# cubey_v2_8step.net
KiCad netlist of a schematic drawn in EAGLE
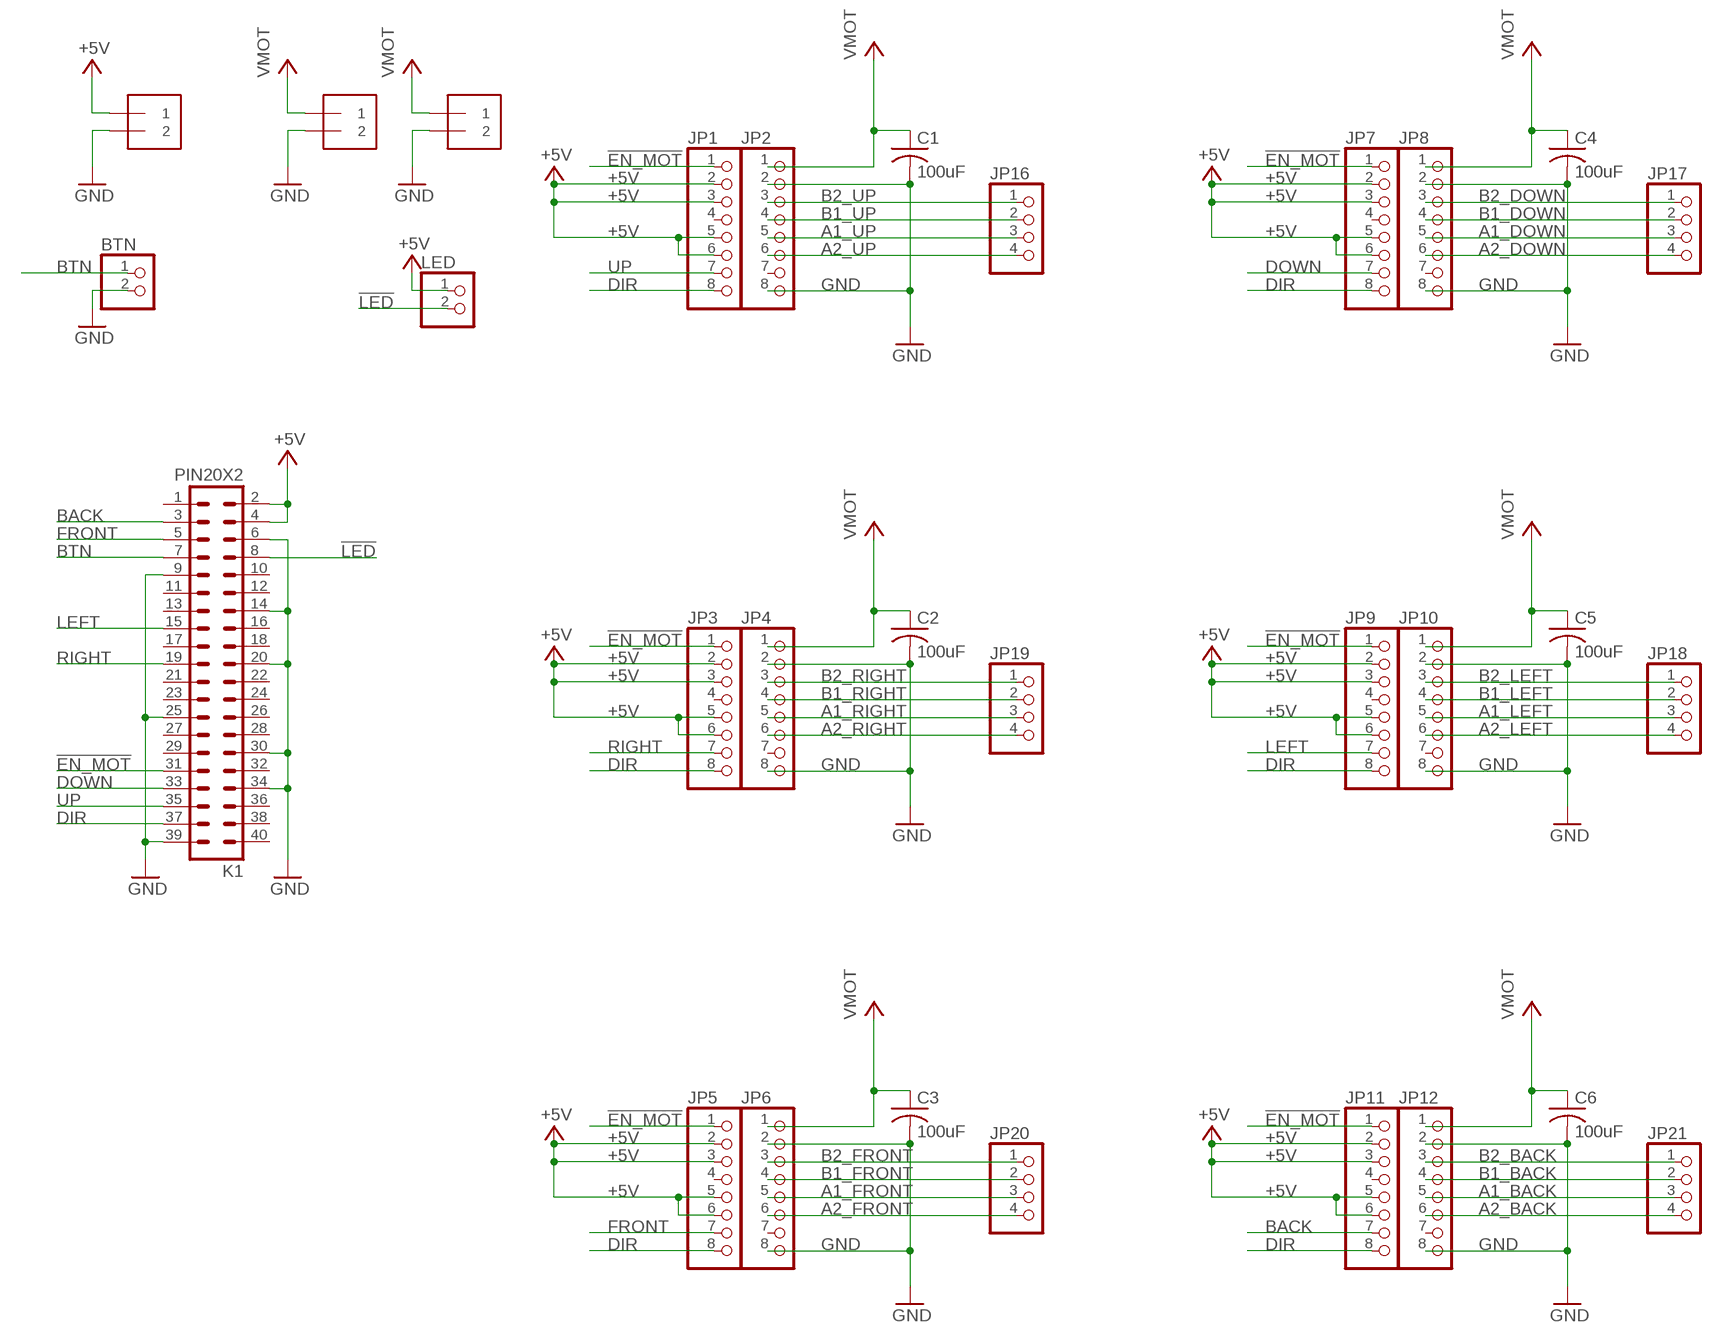
[diagram p0: schematic, sheet 1]

(export (version "E")
  (design (tool "Eeschema 10.0.6"))
  (components
    (comp (ref "5V_PWR")
      (value "1X2-3.5MM")
      (footprint "eagle-import:1X2-3.5MM")
      (libsource (lib "eagle-import") (part "1X2-3.5MM"))
    )
    (comp (ref "BTN")
      (value "PINHD-1X2")
      (footprint "eagle-import:1X02")
      (libsource (lib "eagle-import") (part "PINHD-1X2"))
    )
    (comp (ref "C1")
      (value "100uF")
      (footprint "eagle-import:C025-025X050")
      (libsource (lib "eagle-import") (part "C-US025-025X050"))
    )
    (comp (ref "C2")
      (value "100uF")
      (footprint "eagle-import:C025-025X050")
      (libsource (lib "eagle-import") (part "C-US025-025X050"))
    )
    (comp (ref "C3")
      (value "100uF")
      (footprint "eagle-import:C025-025X050")
      (libsource (lib "eagle-import") (part "C-US025-025X050"))
    )
    (comp (ref "C4")
      (value "100uF")
      (footprint "eagle-import:C025-025X050")
      (libsource (lib "eagle-import") (part "C-US025-025X050"))
    )
    (comp (ref "C5")
      (value "100uF")
      (footprint "eagle-import:C025-025X050")
      (libsource (lib "eagle-import") (part "C-US025-025X050"))
    )
    (comp (ref "C6")
      (value "100uF")
      (footprint "eagle-import:C025-025X050")
      (libsource (lib "eagle-import") (part "C-US025-025X050"))
    )
    (comp (ref "JP1")
      (value "PINHD-1X8")
      (footprint "eagle-import:1X08")
      (libsource (lib "eagle-import") (part "PINHD-1X8"))
    )
    (comp (ref "JP2")
      (value "PINHD-1X8")
      (footprint "eagle-import:1X08")
      (libsource (lib "eagle-import") (part "PINHD-1X8"))
    )
    (comp (ref "JP3")
      (value "PINHD-1X8")
      (footprint "eagle-import:1X08")
      (libsource (lib "eagle-import") (part "PINHD-1X8"))
    )
    (comp (ref "JP4")
      (value "PINHD-1X8")
      (footprint "eagle-import:1X08")
      (libsource (lib "eagle-import") (part "PINHD-1X8"))
    )
    (comp (ref "JP5")
      (value "PINHD-1X8")
      (footprint "eagle-import:1X08")
      (libsource (lib "eagle-import") (part "PINHD-1X8"))
    )
    (comp (ref "JP6")
      (value "PINHD-1X8")
      (footprint "eagle-import:1X08")
      (libsource (lib "eagle-import") (part "PINHD-1X8"))
    )
    (comp (ref "JP7")
      (value "PINHD-1X8")
      (footprint "eagle-import:1X08")
      (libsource (lib "eagle-import") (part "PINHD-1X8"))
    )
    (comp (ref "JP8")
      (value "PINHD-1X8")
      (footprint "eagle-import:1X08")
      (libsource (lib "eagle-import") (part "PINHD-1X8"))
    )
    (comp (ref "JP9")
      (value "PINHD-1X8")
      (footprint "eagle-import:1X08")
      (libsource (lib "eagle-import") (part "PINHD-1X8"))
    )
    (comp (ref "JP10")
      (value "PINHD-1X8")
      (footprint "eagle-import:1X08")
      (libsource (lib "eagle-import") (part "PINHD-1X8"))
    )
    (comp (ref "JP11")
      (value "PINHD-1X8")
      (footprint "eagle-import:1X08")
      (libsource (lib "eagle-import") (part "PINHD-1X8"))
    )
    (comp (ref "JP12")
      (value "PINHD-1X8")
      (footprint "eagle-import:1X08")
      (libsource (lib "eagle-import") (part "PINHD-1X8"))
    )
    (comp (ref "JP16")
      (value "PINHD-1X4")
      (footprint "eagle-import:1X04")
      (libsource (lib "eagle-import") (part "PINHD-1X4"))
    )
    (comp (ref "JP17")
      (value "PINHD-1X4")
      (footprint "eagle-import:1X04")
      (libsource (lib "eagle-import") (part "PINHD-1X4"))
    )
    (comp (ref "JP18")
      (value "PINHD-1X4")
      (footprint "eagle-import:1X04")
      (libsource (lib "eagle-import") (part "PINHD-1X4"))
    )
    (comp (ref "JP19")
      (value "PINHD-1X4")
      (footprint "eagle-import:1X04")
      (libsource (lib "eagle-import") (part "PINHD-1X4"))
    )
    (comp (ref "JP20")
      (value "PINHD-1X4")
      (footprint "eagle-import:1X04")
      (libsource (lib "eagle-import") (part "PINHD-1X4"))
    )
    (comp (ref "JP21")
      (value "PINHD-1X4")
      (footprint "eagle-import:1X04")
      (libsource (lib "eagle-import") (part "PINHD-1X4"))
    )
    (comp (ref "K1")
      (value "PIN20X2")
      (footprint "eagle-import:PIN_20X2")
      (libsource (lib "eagle-import") (part "PIN20X2"))
    )
    (comp (ref "LED")
      (value "PINHD-1X2")
      (footprint "eagle-import:1X02")
      (libsource (lib "eagle-import") (part "PINHD-1X2"))
    )
    (comp (ref "MOT_PWR")
      (value "1X2-3.5MM")
      (footprint "eagle-import:1X2-3.5MM")
      (libsource (lib "eagle-import") (part "1X2-3.5MM"))
    )
    (comp (ref "MOT_PWR1")
      (value "1X2-3.5MM")
      (footprint "eagle-import:1X2-3.5MM")
      (libsource (lib "eagle-import") (part "1X2-3.5MM"))
    )
  )
  (nets
    (net (code "1") (name "+5V") (class "Default")
      (node (ref "5V_PWR") (pin "1") (pinfunction "1_1") (pintype "passive"))
      (node (ref "JP1") (pin "2") (pinfunction "2_2") (pintype "passive"))
      (node (ref "JP1") (pin "3") (pinfunction "3_3") (pintype "passive"))
      (node (ref "JP1") (pin "5") (pinfunction "5_5") (pintype "passive"))
      (node (ref "JP1") (pin "6") (pinfunction "6_6") (pintype "passive"))
      (node (ref "JP11") (pin "2") (pinfunction "2_2") (pintype "passive"))
      (node (ref "JP11") (pin "3") (pinfunction "3_3") (pintype "passive"))
      (node (ref "JP11") (pin "5") (pinfunction "5_5") (pintype "passive"))
      (node (ref "JP11") (pin "6") (pinfunction "6_6") (pintype "passive"))
      (node (ref "JP3") (pin "2") (pinfunction "2_2") (pintype "passive"))
      (node (ref "JP3") (pin "3") (pinfunction "3_3") (pintype "passive"))
      (node (ref "JP3") (pin "5") (pinfunction "5_5") (pintype "passive"))
      (node (ref "JP3") (pin "6") (pinfunction "6_6") (pintype "passive"))
      (node (ref "JP5") (pin "2") (pinfunction "2_2") (pintype "passive"))
      (node (ref "JP5") (pin "3") (pinfunction "3_3") (pintype "passive"))
      (node (ref "JP5") (pin "5") (pinfunction "5_5") (pintype "passive"))
      (node (ref "JP5") (pin "6") (pinfunction "6_6") (pintype "passive"))
      (node (ref "JP7") (pin "2") (pinfunction "2_2") (pintype "passive"))
      (node (ref "JP7") (pin "3") (pinfunction "3_3") (pintype "passive"))
      (node (ref "JP7") (pin "5") (pinfunction "5_5") (pintype "passive"))
      (node (ref "JP7") (pin "6") (pinfunction "6_6") (pintype "passive"))
      (node (ref "JP9") (pin "2") (pinfunction "2_2") (pintype "passive"))
      (node (ref "JP9") (pin "3") (pinfunction "3_3") (pintype "passive"))
      (node (ref "JP9") (pin "5") (pinfunction "5_5") (pintype "passive"))
      (node (ref "JP9") (pin "6") (pinfunction "6_6") (pintype "passive"))
      (node (ref "K1") (pin "2") (pinfunction "2_2") (pintype "passive"))
      (node (ref "K1") (pin "4") (pinfunction "4_4") (pintype "passive"))
      (node (ref "LED") (pin "1") (pinfunction "1_1") (pintype "passive"))
    )
    (net (code "2") (name "/A1_BACK") (class "Default")
      (node (ref "JP12") (pin "5") (pinfunction "5_5") (pintype "passive"))
      (node (ref "JP21") (pin "3") (pinfunction "3_3") (pintype "passive"))
    )
    (net (code "3") (name "/A1_DOWN") (class "Default")
      (node (ref "JP17") (pin "3") (pinfunction "3_3") (pintype "passive"))
      (node (ref "JP8") (pin "5") (pinfunction "5_5") (pintype "passive"))
    )
    (net (code "4") (name "/A1_FRONT") (class "Default")
      (node (ref "JP20") (pin "3") (pinfunction "3_3") (pintype "passive"))
      (node (ref "JP6") (pin "5") (pinfunction "5_5") (pintype "passive"))
    )
    (net (code "5") (name "/A1_LEFT") (class "Default")
      (node (ref "JP10") (pin "5") (pinfunction "5_5") (pintype "passive"))
      (node (ref "JP18") (pin "3") (pinfunction "3_3") (pintype "passive"))
    )
    (net (code "6") (name "/A1_RIGHT") (class "Default")
      (node (ref "JP19") (pin "3") (pinfunction "3_3") (pintype "passive"))
      (node (ref "JP4") (pin "5") (pinfunction "5_5") (pintype "passive"))
    )
    (net (code "7") (name "/A1_UP") (class "Default")
      (node (ref "JP16") (pin "3") (pinfunction "3_3") (pintype "passive"))
      (node (ref "JP2") (pin "5") (pinfunction "5_5") (pintype "passive"))
    )
    (net (code "8") (name "/A2_BACK") (class "Default")
      (node (ref "JP12") (pin "6") (pinfunction "6_6") (pintype "passive"))
      (node (ref "JP21") (pin "4") (pinfunction "4_4") (pintype "passive"))
    )
    (net (code "9") (name "/A2_DOWN") (class "Default")
      (node (ref "JP17") (pin "4") (pinfunction "4_4") (pintype "passive"))
      (node (ref "JP8") (pin "6") (pinfunction "6_6") (pintype "passive"))
    )
    (net (code "10") (name "/A2_FRONT") (class "Default")
      (node (ref "JP20") (pin "4") (pinfunction "4_4") (pintype "passive"))
      (node (ref "JP6") (pin "6") (pinfunction "6_6") (pintype "passive"))
    )
    (net (code "11") (name "/A2_LEFT") (class "Default")
      (node (ref "JP10") (pin "6") (pinfunction "6_6") (pintype "passive"))
      (node (ref "JP18") (pin "4") (pinfunction "4_4") (pintype "passive"))
    )
    (net (code "12") (name "/A2_RIGHT") (class "Default")
      (node (ref "JP19") (pin "4") (pinfunction "4_4") (pintype "passive"))
      (node (ref "JP4") (pin "6") (pinfunction "6_6") (pintype "passive"))
    )
    (net (code "13") (name "/A2_UP") (class "Default")
      (node (ref "JP16") (pin "4") (pinfunction "4_4") (pintype "passive"))
      (node (ref "JP2") (pin "6") (pinfunction "6_6") (pintype "passive"))
    )
    (net (code "14") (name "/B1_BACK") (class "Default")
      (node (ref "JP12") (pin "4") (pinfunction "4_4") (pintype "passive"))
      (node (ref "JP21") (pin "2") (pinfunction "2_2") (pintype "passive"))
    )
    (net (code "15") (name "/B1_DOWN") (class "Default")
      (node (ref "JP17") (pin "2") (pinfunction "2_2") (pintype "passive"))
      (node (ref "JP8") (pin "4") (pinfunction "4_4") (pintype "passive"))
    )
    (net (code "16") (name "/B1_FRONT") (class "Default")
      (node (ref "JP20") (pin "2") (pinfunction "2_2") (pintype "passive"))
      (node (ref "JP6") (pin "4") (pinfunction "4_4") (pintype "passive"))
    )
    (net (code "17") (name "/B1_LEFT") (class "Default")
      (node (ref "JP10") (pin "4") (pinfunction "4_4") (pintype "passive"))
      (node (ref "JP18") (pin "2") (pinfunction "2_2") (pintype "passive"))
    )
    (net (code "18") (name "/B1_RIGHT") (class "Default")
      (node (ref "JP19") (pin "2") (pinfunction "2_2") (pintype "passive"))
      (node (ref "JP4") (pin "4") (pinfunction "4_4") (pintype "passive"))
    )
    (net (code "19") (name "/B1_UP") (class "Default")
      (node (ref "JP16") (pin "2") (pinfunction "2_2") (pintype "passive"))
      (node (ref "JP2") (pin "4") (pinfunction "4_4") (pintype "passive"))
    )
    (net (code "20") (name "/B2_BACK") (class "Default")
      (node (ref "JP12") (pin "3") (pinfunction "3_3") (pintype "passive"))
      (node (ref "JP21") (pin "1") (pinfunction "1_1") (pintype "passive"))
    )
    (net (code "21") (name "/B2_DOWN") (class "Default")
      (node (ref "JP17") (pin "1") (pinfunction "1_1") (pintype "passive"))
      (node (ref "JP8") (pin "3") (pinfunction "3_3") (pintype "passive"))
    )
    (net (code "22") (name "/B2_FRONT") (class "Default")
      (node (ref "JP20") (pin "1") (pinfunction "1_1") (pintype "passive"))
      (node (ref "JP6") (pin "3") (pinfunction "3_3") (pintype "passive"))
    )
    (net (code "23") (name "/B2_LEFT") (class "Default")
      (node (ref "JP10") (pin "3") (pinfunction "3_3") (pintype "passive"))
      (node (ref "JP18") (pin "1") (pinfunction "1_1") (pintype "passive"))
    )
    (net (code "24") (name "/B2_RIGHT") (class "Default")
      (node (ref "JP19") (pin "1") (pinfunction "1_1") (pintype "passive"))
      (node (ref "JP4") (pin "3") (pinfunction "3_3") (pintype "passive"))
    )
    (net (code "25") (name "/B2_UP") (class "Default")
      (node (ref "JP16") (pin "1") (pinfunction "1_1") (pintype "passive"))
      (node (ref "JP2") (pin "3") (pinfunction "3_3") (pintype "passive"))
    )
    (net (code "26") (name "/BACK") (class "Default")
      (node (ref "JP11") (pin "7") (pinfunction "7_7") (pintype "passive"))
      (node (ref "K1") (pin "3") (pinfunction "3_3") (pintype "passive"))
    )
    (net (code "27") (name "/BTN") (class "Default")
      (node (ref "BTN") (pin "1") (pinfunction "1_1") (pintype "passive"))
      (node (ref "K1") (pin "7") (pinfunction "7_7") (pintype "passive"))
    )
    (net (code "28") (name "/DIR") (class "Default")
      (node (ref "JP1") (pin "8") (pinfunction "8_8") (pintype "passive"))
      (node (ref "JP11") (pin "8") (pinfunction "8_8") (pintype "passive"))
      (node (ref "JP3") (pin "8") (pinfunction "8_8") (pintype "passive"))
      (node (ref "JP5") (pin "8") (pinfunction "8_8") (pintype "passive"))
      (node (ref "JP7") (pin "8") (pinfunction "8_8") (pintype "passive"))
      (node (ref "JP9") (pin "8") (pinfunction "8_8") (pintype "passive"))
      (node (ref "K1") (pin "37") (pinfunction "37_37") (pintype "passive"))
    )
    (net (code "29") (name "/DOWN") (class "Default")
      (node (ref "JP7") (pin "7") (pinfunction "7_7") (pintype "passive"))
      (node (ref "K1") (pin "33") (pinfunction "33_33") (pintype "passive"))
    )
    (net (code "30") (name "/FRONT") (class "Default")
      (node (ref "JP5") (pin "7") (pinfunction "7_7") (pintype "passive"))
      (node (ref "K1") (pin "5") (pinfunction "5_5") (pintype "passive"))
    )
    (net (code "31") (name "/LEFT") (class "Default")
      (node (ref "JP9") (pin "7") (pinfunction "7_7") (pintype "passive"))
      (node (ref "K1") (pin "15") (pinfunction "15_15") (pintype "passive"))
    )
    (net (code "32") (name "/RIGHT") (class "Default")
      (node (ref "JP3") (pin "7") (pinfunction "7_7") (pintype "passive"))
      (node (ref "K1") (pin "19") (pinfunction "19_19") (pintype "passive"))
    )
    (net (code "33") (name "/UP") (class "Default")
      (node (ref "JP1") (pin "7") (pinfunction "7_7") (pintype "passive"))
      (node (ref "K1") (pin "35") (pinfunction "35_35") (pintype "passive"))
    )
    (net (code "34") (name "/~{EN_MOT}") (class "Default")
      (node (ref "JP1") (pin "1") (pinfunction "1_1") (pintype "passive"))
      (node (ref "JP11") (pin "1") (pinfunction "1_1") (pintype "passive"))
      (node (ref "JP3") (pin "1") (pinfunction "1_1") (pintype "passive"))
      (node (ref "JP5") (pin "1") (pinfunction "1_1") (pintype "passive"))
      (node (ref "JP7") (pin "1") (pinfunction "1_1") (pintype "passive"))
      (node (ref "JP9") (pin "1") (pinfunction "1_1") (pintype "passive"))
      (node (ref "K1") (pin "31") (pinfunction "31_31") (pintype "passive"))
    )
    (net (code "35") (name "/~{LED}") (class "Default")
      (node (ref "K1") (pin "8") (pinfunction "8_8") (pintype "passive"))
      (node (ref "LED") (pin "2") (pinfunction "2_2") (pintype "passive"))
    )
    (net (code "36") (name "GND") (class "Default")
      (node (ref "5V_PWR") (pin "2") (pinfunction "2_2") (pintype "passive"))
      (node (ref "BTN") (pin "2") (pinfunction "2_2") (pintype "passive"))
      (node (ref "C1") (pin "2") (pinfunction "2_2") (pintype "passive"))
      (node (ref "C2") (pin "2") (pinfunction "2_2") (pintype "passive"))
      (node (ref "C3") (pin "2") (pinfunction "2_2") (pintype "passive"))
      (node (ref "C4") (pin "2") (pinfunction "2_2") (pintype "passive"))
      (node (ref "C5") (pin "2") (pinfunction "2_2") (pintype "passive"))
      (node (ref "C6") (pin "2") (pinfunction "2_2") (pintype "passive"))
      (node (ref "JP10") (pin "2") (pinfunction "2_2") (pintype "passive"))
      (node (ref "JP10") (pin "8") (pinfunction "8_8") (pintype "passive"))
      (node (ref "JP12") (pin "2") (pinfunction "2_2") (pintype "passive"))
      (node (ref "JP12") (pin "8") (pinfunction "8_8") (pintype "passive"))
      (node (ref "JP2") (pin "2") (pinfunction "2_2") (pintype "passive"))
      (node (ref "JP2") (pin "8") (pinfunction "8_8") (pintype "passive"))
      (node (ref "JP4") (pin "2") (pinfunction "2_2") (pintype "passive"))
      (node (ref "JP4") (pin "8") (pinfunction "8_8") (pintype "passive"))
      (node (ref "JP6") (pin "2") (pinfunction "2_2") (pintype "passive"))
      (node (ref "JP6") (pin "8") (pinfunction "8_8") (pintype "passive"))
      (node (ref "JP8") (pin "2") (pinfunction "2_2") (pintype "passive"))
      (node (ref "JP8") (pin "8") (pinfunction "8_8") (pintype "passive"))
      (node (ref "K1") (pin "14") (pinfunction "14_14") (pintype "passive"))
      (node (ref "K1") (pin "20") (pinfunction "20_20") (pintype "passive"))
      (node (ref "K1") (pin "25") (pinfunction "25_25") (pintype "passive"))
      (node (ref "K1") (pin "30") (pinfunction "30_30") (pintype "passive"))
      (node (ref "K1") (pin "34") (pinfunction "34_34") (pintype "passive"))
      (node (ref "K1") (pin "39") (pinfunction "39_39") (pintype "passive"))
      (node (ref "K1") (pin "6") (pinfunction "6_6") (pintype "passive"))
      (node (ref "K1") (pin "9") (pinfunction "9_9") (pintype "passive"))
      (node (ref "MOT_PWR") (pin "2") (pinfunction "2_2") (pintype "passive"))
      (node (ref "MOT_PWR1") (pin "2") (pinfunction "2_2") (pintype "passive"))
    )
    (net (code "37") (name "VMOT") (class "Default")
      (node (ref "C1") (pin "1") (pinfunction "1_1") (pintype "passive"))
      (node (ref "C2") (pin "1") (pinfunction "1_1") (pintype "passive"))
      (node (ref "C3") (pin "1") (pinfunction "1_1") (pintype "passive"))
      (node (ref "C4") (pin "1") (pinfunction "1_1") (pintype "passive"))
      (node (ref "C5") (pin "1") (pinfunction "1_1") (pintype "passive"))
      (node (ref "C6") (pin "1") (pinfunction "1_1") (pintype "passive"))
      (node (ref "JP10") (pin "1") (pinfunction "1_1") (pintype "passive"))
      (node (ref "JP12") (pin "1") (pinfunction "1_1") (pintype "passive"))
      (node (ref "JP2") (pin "1") (pinfunction "1_1") (pintype "passive"))
      (node (ref "JP4") (pin "1") (pinfunction "1_1") (pintype "passive"))
      (node (ref "JP6") (pin "1") (pinfunction "1_1") (pintype "passive"))
      (node (ref "JP8") (pin "1") (pinfunction "1_1") (pintype "passive"))
      (node (ref "MOT_PWR") (pin "1") (pinfunction "1_1") (pintype "passive"))
      (node (ref "MOT_PWR1") (pin "1") (pinfunction "1_1") (pintype "passive"))
    )
    (net (code "38") (name "unconnected-(JP1-Pad4)") (class "Default")
      (node (ref "JP1") (pin "4") (pinfunction "4_4") (pintype "passive"))
    )
    (net (code "39") (name "unconnected-(JP2-Pad7)") (class "Default")
      (node (ref "JP2") (pin "7") (pinfunction "7_7") (pintype "passive"))
    )
    (net (code "40") (name "unconnected-(JP3-Pad4)") (class "Default")
      (node (ref "JP3") (pin "4") (pinfunction "4_4") (pintype "passive"))
    )
    (net (code "41") (name "unconnected-(JP4-Pad7)") (class "Default")
      (node (ref "JP4") (pin "7") (pinfunction "7_7") (pintype "passive"))
    )
    (net (code "42") (name "unconnected-(JP5-Pad4)") (class "Default")
      (node (ref "JP5") (pin "4") (pinfunction "4_4") (pintype "passive"))
    )
    (net (code "43") (name "unconnected-(JP6-Pad7)") (class "Default")
      (node (ref "JP6") (pin "7") (pinfunction "7_7") (pintype "passive"))
    )
    (net (code "44") (name "unconnected-(JP7-Pad4)") (class "Default")
      (node (ref "JP7") (pin "4") (pinfunction "4_4") (pintype "passive"))
    )
    (net (code "45") (name "unconnected-(JP8-Pad7)") (class "Default")
      (node (ref "JP8") (pin "7") (pinfunction "7_7") (pintype "passive"))
    )
    (net (code "46") (name "unconnected-(JP9-Pad4)") (class "Default")
      (node (ref "JP9") (pin "4") (pinfunction "4_4") (pintype "passive"))
    )
    (net (code "47") (name "unconnected-(JP10-Pad7)") (class "Default")
      (node (ref "JP10") (pin "7") (pinfunction "7_7") (pintype "passive"))
    )
    (net (code "48") (name "unconnected-(JP11-Pad4)") (class "Default")
      (node (ref "JP11") (pin "4") (pinfunction "4_4") (pintype "passive"))
    )
    (net (code "49") (name "unconnected-(JP12-Pad7)") (class "Default")
      (node (ref "JP12") (pin "7") (pinfunction "7_7") (pintype "passive"))
    )
    (net (code "50") (name "unconnected-(K1-Pad1)") (class "Default")
      (node (ref "K1") (pin "1") (pinfunction "1_1") (pintype "passive"))
    )
    (net (code "51") (name "unconnected-(K1-Pad10)") (class "Default")
      (node (ref "K1") (pin "10") (pinfunction "10_10") (pintype "passive"))
    )
    (net (code "52") (name "unconnected-(K1-Pad11)") (class "Default")
      (node (ref "K1") (pin "11") (pinfunction "11_11") (pintype "passive"))
    )
    (net (code "53") (name "unconnected-(K1-Pad12)") (class "Default")
      (node (ref "K1") (pin "12") (pinfunction "12_12") (pintype "passive"))
    )
    (net (code "54") (name "unconnected-(K1-Pad13)") (class "Default")
      (node (ref "K1") (pin "13") (pinfunction "13_13") (pintype "passive"))
    )
    (net (code "55") (name "unconnected-(K1-Pad16)") (class "Default")
      (node (ref "K1") (pin "16") (pinfunction "16_16") (pintype "passive"))
    )
    (net (code "56") (name "unconnected-(K1-Pad17)") (class "Default")
      (node (ref "K1") (pin "17") (pinfunction "17_17") (pintype "passive"))
    )
    (net (code "57") (name "unconnected-(K1-Pad18)") (class "Default")
      (node (ref "K1") (pin "18") (pinfunction "18_18") (pintype "passive"))
    )
    (net (code "58") (name "unconnected-(K1-Pad21)") (class "Default")
      (node (ref "K1") (pin "21") (pinfunction "21_21") (pintype "passive"))
    )
    (net (code "59") (name "unconnected-(K1-Pad22)") (class "Default")
      (node (ref "K1") (pin "22") (pinfunction "22_22") (pintype "passive"))
    )
    (net (code "60") (name "unconnected-(K1-Pad23)") (class "Default")
      (node (ref "K1") (pin "23") (pinfunction "23_23") (pintype "passive"))
    )
    (net (code "61") (name "unconnected-(K1-Pad24)") (class "Default")
      (node (ref "K1") (pin "24") (pinfunction "24_24") (pintype "passive"))
    )
    (net (code "62") (name "unconnected-(K1-Pad26)") (class "Default")
      (node (ref "K1") (pin "26") (pinfunction "26_26") (pintype "passive"))
    )
    (net (code "63") (name "unconnected-(K1-Pad27)") (class "Default")
      (node (ref "K1") (pin "27") (pinfunction "27_27") (pintype "passive"))
    )
    (net (code "64") (name "unconnected-(K1-Pad28)") (class "Default")
      (node (ref "K1") (pin "28") (pinfunction "28_28") (pintype "passive"))
    )
    (net (code "65") (name "unconnected-(K1-Pad29)") (class "Default")
      (node (ref "K1") (pin "29") (pinfunction "29_29") (pintype "passive"))
    )
    (net (code "66") (name "unconnected-(K1-Pad32)") (class "Default")
      (node (ref "K1") (pin "32") (pinfunction "32_32") (pintype "passive"))
    )
    (net (code "67") (name "unconnected-(K1-Pad36)") (class "Default")
      (node (ref "K1") (pin "36") (pinfunction "36_36") (pintype "passive"))
    )
    (net (code "68") (name "unconnected-(K1-Pad38)") (class "Default")
      (node (ref "K1") (pin "38") (pinfunction "38_38") (pintype "passive"))
    )
    (net (code "69") (name "unconnected-(K1-Pad40)") (class "Default")
      (node (ref "K1") (pin "40") (pinfunction "40_40") (pintype "passive"))
    )
  )
)
